# Nintendo_3DS_USB-C.net
KiCad netlist of a schematic drawn in EAGLE
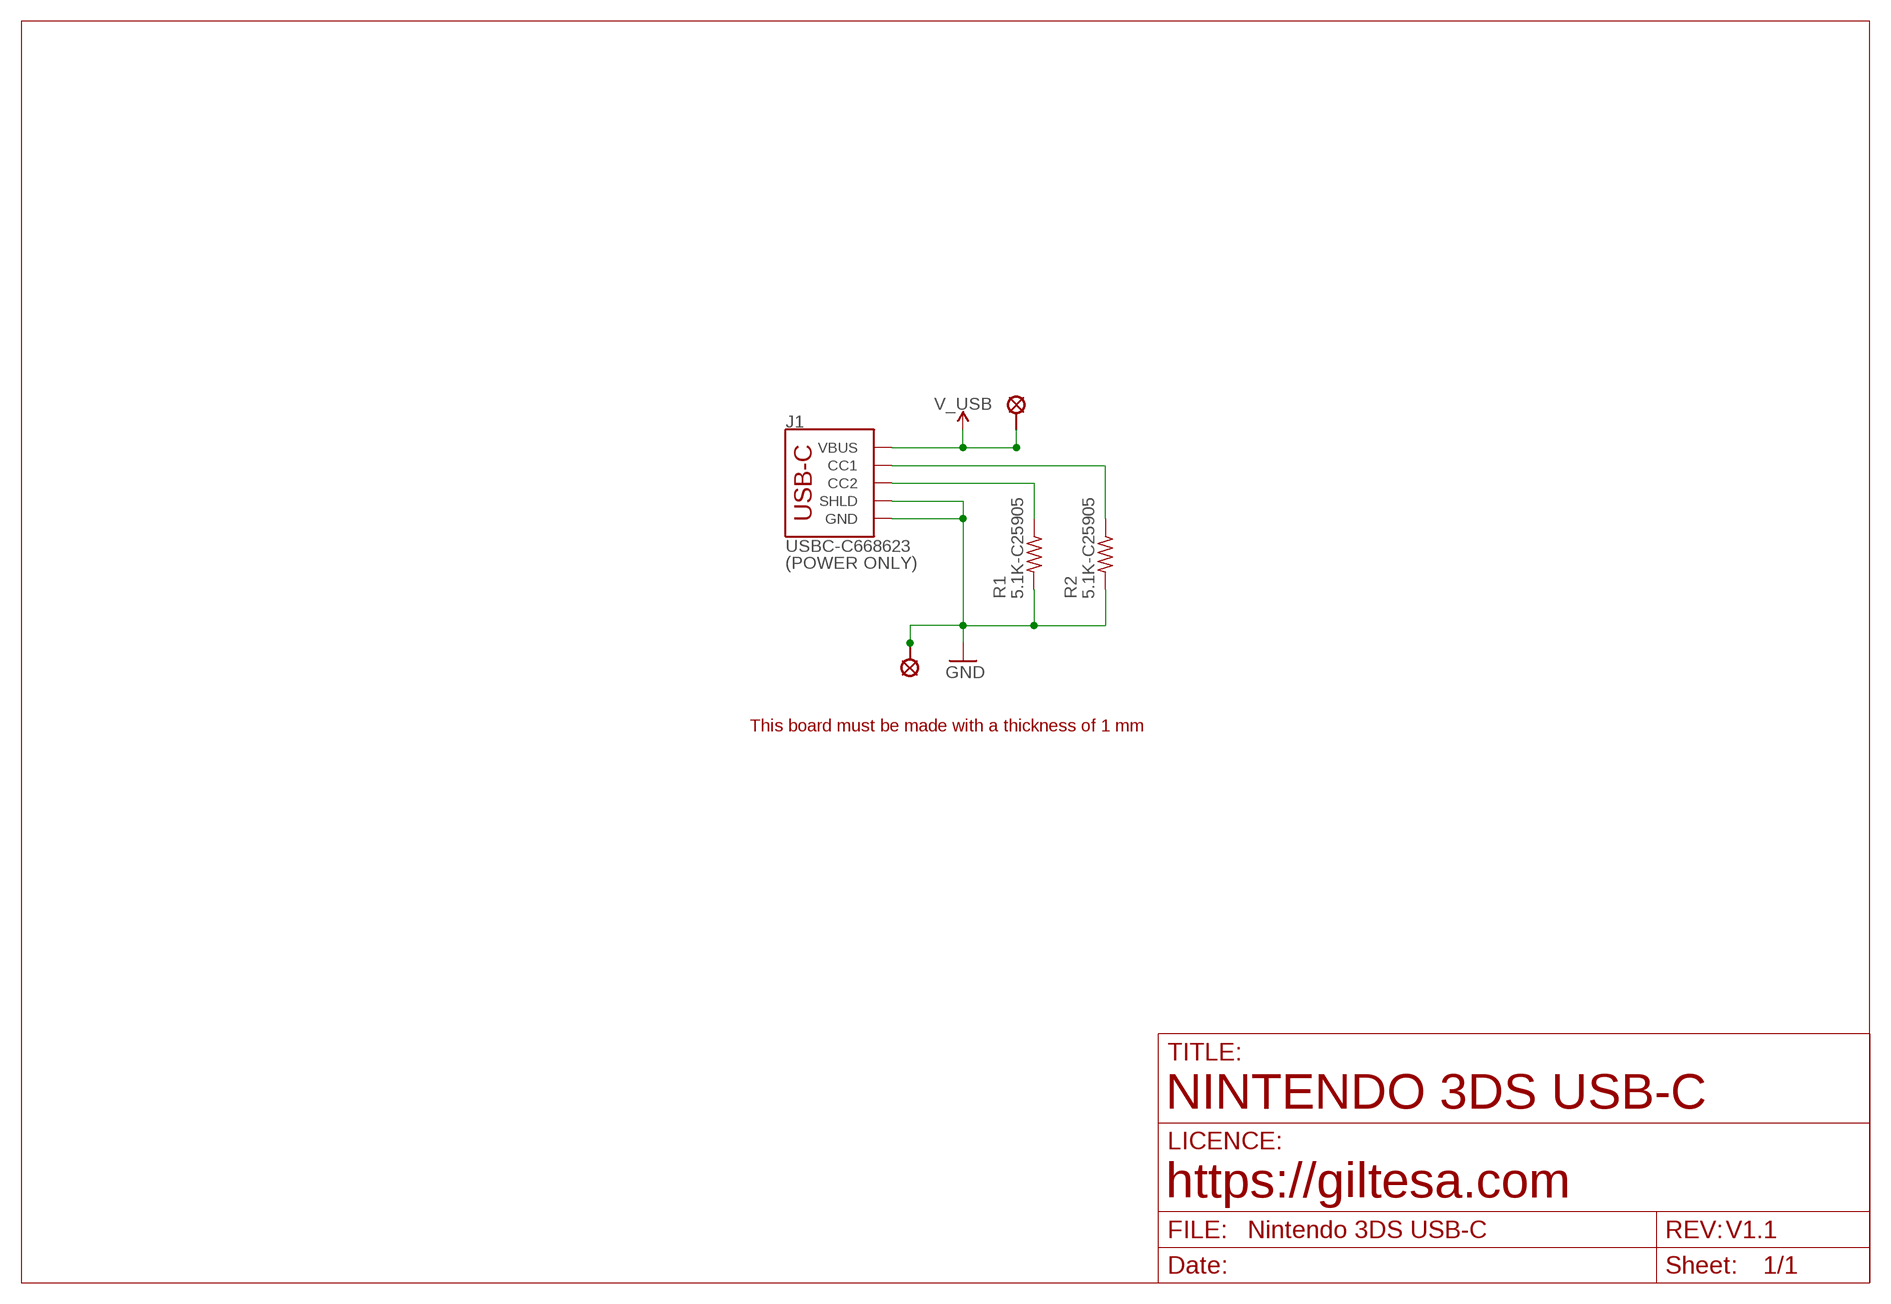
[diagram p0: schematic, sheet 1]

(export (version "E")
  (design (tool "Eeschema 10.0.6"))
  (components
    (comp (ref "J1")
      (value "USBC-C668623")
      (footprint "eagle-import:USB-C_6P")
      (libsource (lib "eagle-import") (part "USB-CPOWER"))
    )
    (comp (ref "R1")
      (value "5.1K-C25905")
      (footprint "eagle-import:R0402")
      (libsource (lib "eagle-import") (part "R0402"))
    )
    (comp (ref "R2")
      (value "5.1K-C25905")
      (footprint "eagle-import:R0402")
      (libsource (lib "eagle-import") (part "R0402"))
    )
    (comp (ref "U$2")
      (value "PAD_1.0H")
      (footprint "eagle-import:PAD_1.0_HALF_MASK")
      (libsource (lib "eagle-import") (part "PAD_1.0H"))
    )
    (comp (ref "U$3")
      (value "PAD_1.0H")
      (footprint "eagle-import:PAD_1.0_HALF_MASK")
      (libsource (lib "eagle-import") (part "PAD_1.0H"))
    )
    (comp (ref "U$4")
      (value "PAD_1.0H")
      (footprint "eagle-import:PAD_1.0_HALF_MASK")
      (libsource (lib "eagle-import") (part "PAD_1.0H"))
    )
    (comp (ref "U$6")
      (value "PAD_1.0H")
      (footprint "eagle-import:PAD_1.0_HALF_MASK")
      (libsource (lib "eagle-import") (part "PAD_1.0H"))
    )
    (comp (ref "U$7")
      (value "PAD_1.0H")
      (footprint "eagle-import:PAD_1.0_HALF_MASK")
      (libsource (lib "eagle-import") (part "PAD_1.0H"))
    )
    (comp (ref "U$8")
      (value "PAD_1.0H")
      (footprint "eagle-import:PAD_1.0_HALF_MASK")
      (libsource (lib "eagle-import") (part "PAD_1.0H"))
    )
  )
  (nets
    (net (code "1") (name "GND") (class "Default")
      (node (ref "J1") (pin "GND1") (pinfunction "GND_GND1") (pintype "bidirectional"))
      (node (ref "J1") (pin "GND2") (pinfunction "GND_GND2") (pintype "bidirectional"))
      (node (ref "J1") (pin "SHLD1") (pinfunction "SHLD_SHLD1") (pintype "bidirectional"))
      (node (ref "J1") (pin "SHLD2") (pinfunction "SHLD_SHLD2") (pintype "bidirectional"))
      (node (ref "J1") (pin "SHLD3") (pinfunction "SHLD_SHLD3") (pintype "bidirectional"))
      (node (ref "J1") (pin "SHLD4") (pinfunction "SHLD_SHLD4") (pintype "bidirectional"))
      (node (ref "J1") (pin "SHLD5") (pinfunction "SHLD_SHLD5") (pintype "bidirectional"))
      (node (ref "J1") (pin "SHLD6") (pinfunction "SHLD_SHLD6") (pintype "bidirectional"))
      (node (ref "J1") (pin "SHLD7") (pinfunction "SHLD_SHLD7") (pintype "bidirectional"))
      (node (ref "J1") (pin "SHLD8") (pinfunction "SHLD_SHLD8") (pintype "bidirectional"))
      (node (ref "R1") (pin "2") (pinfunction "2_2") (pintype "passive"))
      (node (ref "R2") (pin "2") (pinfunction "2_2") (pintype "passive"))
      (node (ref "U$4") (pin "P$1") (pinfunction "P$1_P$1") (pintype "bidirectional"))
      (node (ref "U$6") (pin "P$1") (pinfunction "P$1_P$1") (pintype "bidirectional"))
      (node (ref "U$7") (pin "P$1") (pinfunction "P$1_P$1") (pintype "bidirectional"))
      (node (ref "U$8") (pin "P$1") (pinfunction "P$1_P$1") (pintype "bidirectional"))
    )
    (net (code "2") (name "Net-(J1-CC1)") (class "Default")
      (node (ref "J1") (pin "A5") (pinfunction "CC1_A5") (pintype "bidirectional"))
      (node (ref "R2") (pin "1") (pinfunction "1_1") (pintype "passive"))
    )
    (net (code "3") (name "Net-(J1-CC2)") (class "Default")
      (node (ref "J1") (pin "B5") (pinfunction "CC2_B5") (pintype "bidirectional"))
      (node (ref "R1") (pin "1") (pinfunction "1_1") (pintype "passive"))
    )
    (net (code "4") (name "V_USB") (class "Default")
      (node (ref "J1") (pin "VBUS1") (pinfunction "VBUS_VBUS1") (pintype "bidirectional"))
      (node (ref "J1") (pin "VBUS2") (pinfunction "VBUS_VBUS2") (pintype "bidirectional"))
      (node (ref "U$2") (pin "P$1") (pinfunction "P$1_P$1") (pintype "bidirectional"))
      (node (ref "U$3") (pin "P$1") (pinfunction "P$1_P$1") (pintype "bidirectional"))
    )
  )
)
